# Schematic.net
KiCad netlist of a schematic drawn in Altium Designer
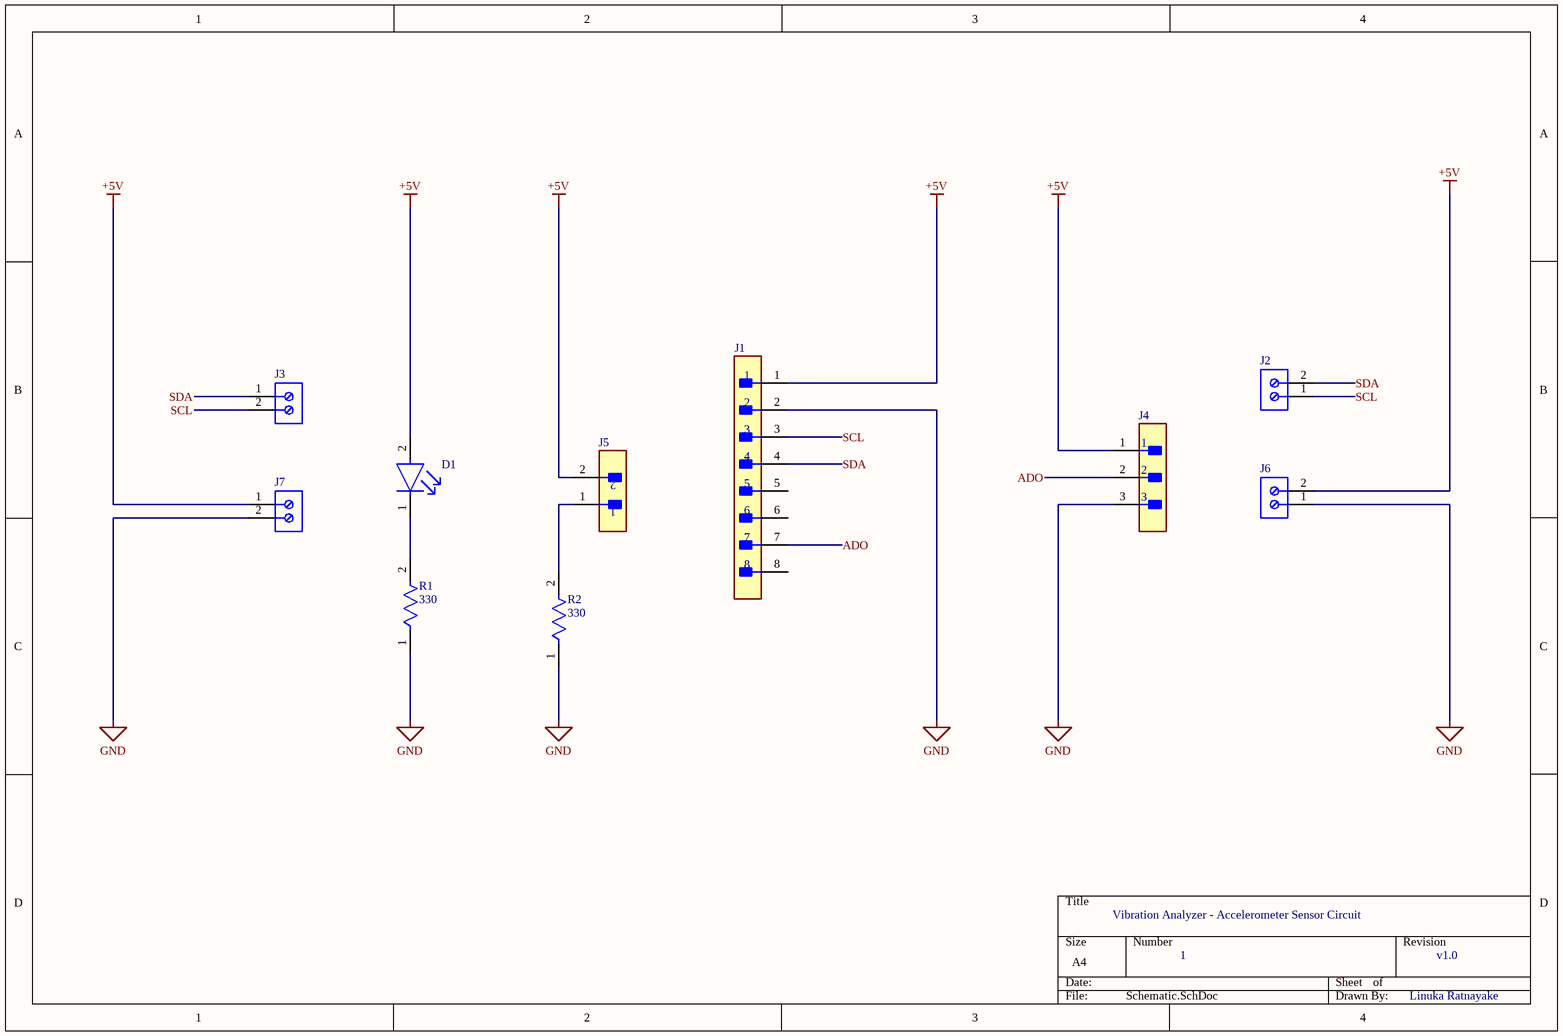
[diagram p0: Schematic.SchDoc]

(export (version "E")
  (design (tool "Eeschema 10.0.6"))
  (components
    (comp (ref "D1")
      (value "HSMG-C150")
      (footprint "FP-HSMG-C150-MFG")
      (description "LED GREEN DIFFUSED 1206 SMD")
      (fields
        (field (name "MANUFACTURER") "Broadcom")
        (field (name "OCTOPART") "https://octopart.com/hsmg-c150-broadcom-71131304")
      )
      (libsource (lib "Altium Content Vault") (part "8706943c75ba83719d021d2fdc84c58"))
    )
    (comp (ref "J1")
      (value "22-29-2081")
      (footprint "FP-22-29-2081-MFG")
      (libsource (lib "Altium Content Vault") (part "99ec2b232beb5d2356d4d77f6a047f0"))
    )
    (comp (ref "J2")
      (value "691214110002")
      (footprint "691214110002")
      (fields (field (name "VOLTAGE") "300V"))
      (libsource (lib "Altium Content Vault") (part "TBL - 1R - 02P - Screw"))
    )
    (comp (ref "J3")
      (value "691214110002")
      (footprint "691214110002")
      (fields (field (name "VOLTAGE") "300V"))
      (libsource (lib "Altium Content Vault") (part "TBL - 1R - 02P - Screw"))
    )
    (comp (ref "J4")
      (value "90120-0763")
      (footprint "FP-90120-0763-MFG")
      (description "CONN HEADER VERT 3POS 2.54MM")
      (fields
        (field (name "MANUFACTURER") "Molex")
        (field (name "OCTOPART") "https://octopart.com/90120-0763-molex-655433")
      )
      (libsource (lib "Altium Content Vault") (part "0d3f023dd272f625e17a2be33dea85f"))
    )
    (comp (ref "J5")
      (value "B2B-XH-A(LF)(SN)")
      (footprint "FP-B2B-XH-A_LF_SN-MFG")
      (description "CONN HEADER VERT 2POS 2.5MM")
      (libsource (lib "Altium Content Vault") (part "3bc925449376181038e59eaffc5286c"))
    )
    (comp (ref "J6")
      (value "691214110002")
      (footprint "691214110002")
      (fields (field (name "VOLTAGE") "300V"))
      (libsource (lib "Altium Content Vault") (part "TBL - 1R - 02P - Screw"))
    )
    (comp (ref "J7")
      (value "691214110002")
      (footprint "691214110002")
      (fields (field (name "VOLTAGE") "300V"))
      (libsource (lib "Altium Content Vault") (part "TBL - 1R - 02P - Screw"))
    )
    (comp (ref "R1")
      (value "MCR18EZPF30R0")
      (footprint "FP-MCR18-IPC_B")
      (description "Thick Film Chip Resistor, 1206, 30Ω, 1%, 100ppm/°C, 0.25W, 200V")
      (fields (field (name "RESISTANCE") "330") (field (name "TOLERANCE") "1%"))
      (libsource (lib "Altium Content Vault") (part "1029c3af85768c4190bb7ad29bc67b5"))
    )
    (comp (ref "R2")
      (value "MCR18EZPF30R0")
      (footprint "FP-MCR18-IPC_B")
      (description "Thick Film Chip Resistor, 1206, 30Ω, 1%, 100ppm/°C, 0.25W, 200V")
      (fields (field (name "RESISTANCE") "330") (field (name "TOLERANCE") "1%"))
      (libsource (lib "Altium Content Vault") (part "1029c3af85768c4190bb7ad29bc67b5"))
    )
  )
  (nets
    (net (code "1") (name "+5V") (class "Default")
      (node (ref "D1") (pin "2") (pinfunction "A_2") (pintype "passive"))
      (node (ref "J1") (pin "1") (pinfunction "1_1") (pintype "passive"))
      (node (ref "J4") (pin "1") (pinfunction "1_1") (pintype "passive"))
      (node (ref "J5") (pin "2") (pinfunction "2_2") (pintype "passive"))
      (node (ref "J6") (pin "2") (pinfunction "2_2") (pintype "passive"))
      (node (ref "J7") (pin "1") (pinfunction "1_1") (pintype "passive"))
    )
    (net (code "2") (name "/ADO") (class "Default")
      (node (ref "J1") (pin "7") (pinfunction "7_7") (pintype "passive"))
      (node (ref "J4") (pin "2") (pinfunction "2_2") (pintype "passive"))
    )
    (net (code "3") (name "/SCL") (class "Default")
      (node (ref "J1") (pin "3") (pinfunction "3_3") (pintype "passive"))
      (node (ref "J2") (pin "1") (pinfunction "1_1") (pintype "passive"))
      (node (ref "J3") (pin "2") (pinfunction "2_2") (pintype "passive"))
    )
    (net (code "4") (name "/SDA") (class "Default")
      (node (ref "J1") (pin "4") (pinfunction "4_4") (pintype "passive"))
      (node (ref "J2") (pin "2") (pinfunction "2_2") (pintype "passive"))
      (node (ref "J3") (pin "1") (pinfunction "1_1") (pintype "passive"))
    )
    (net (code "5") (name "GND") (class "Default")
      (node (ref "J1") (pin "2") (pinfunction "2_2") (pintype "passive"))
      (node (ref "J4") (pin "3") (pinfunction "3_3") (pintype "passive"))
      (node (ref "J6") (pin "1") (pinfunction "1_1") (pintype "passive"))
      (node (ref "J7") (pin "2") (pinfunction "2_2") (pintype "passive"))
      (node (ref "R1") (pin "1") (pinfunction "1_1") (pintype "passive"))
      (node (ref "R2") (pin "1") (pinfunction "1_1") (pintype "passive"))
    )
    (net (code "6") (name "Net-(D1-C)") (class "Default")
      (node (ref "D1") (pin "1") (pinfunction "C_1") (pintype "passive"))
      (node (ref "R1") (pin "2") (pinfunction "2_2") (pintype "passive"))
    )
    (net (code "7") (name "Net-(J5-Pad1)") (class "Default")
      (node (ref "J5") (pin "1") (pinfunction "1_1") (pintype "passive"))
      (node (ref "R2") (pin "2") (pinfunction "2_2") (pintype "passive"))
    )
    (net (code "8") (name "unconnected-(J1-Pad5)") (class "Default")
      (node (ref "J1") (pin "5") (pinfunction "5_5") (pintype "passive"))
    )
    (net (code "9") (name "unconnected-(J1-Pad6)") (class "Default")
      (node (ref "J1") (pin "6") (pinfunction "6_6") (pintype "passive"))
    )
    (net (code "10") (name "unconnected-(J1-Pad8)") (class "Default")
      (node (ref "J1") (pin "8") (pinfunction "8_8") (pintype "passive"))
    )
  )
)
